# 06_-_SATA_CFAST.net
KiCad netlist of a schematic drawn in Altium Designer
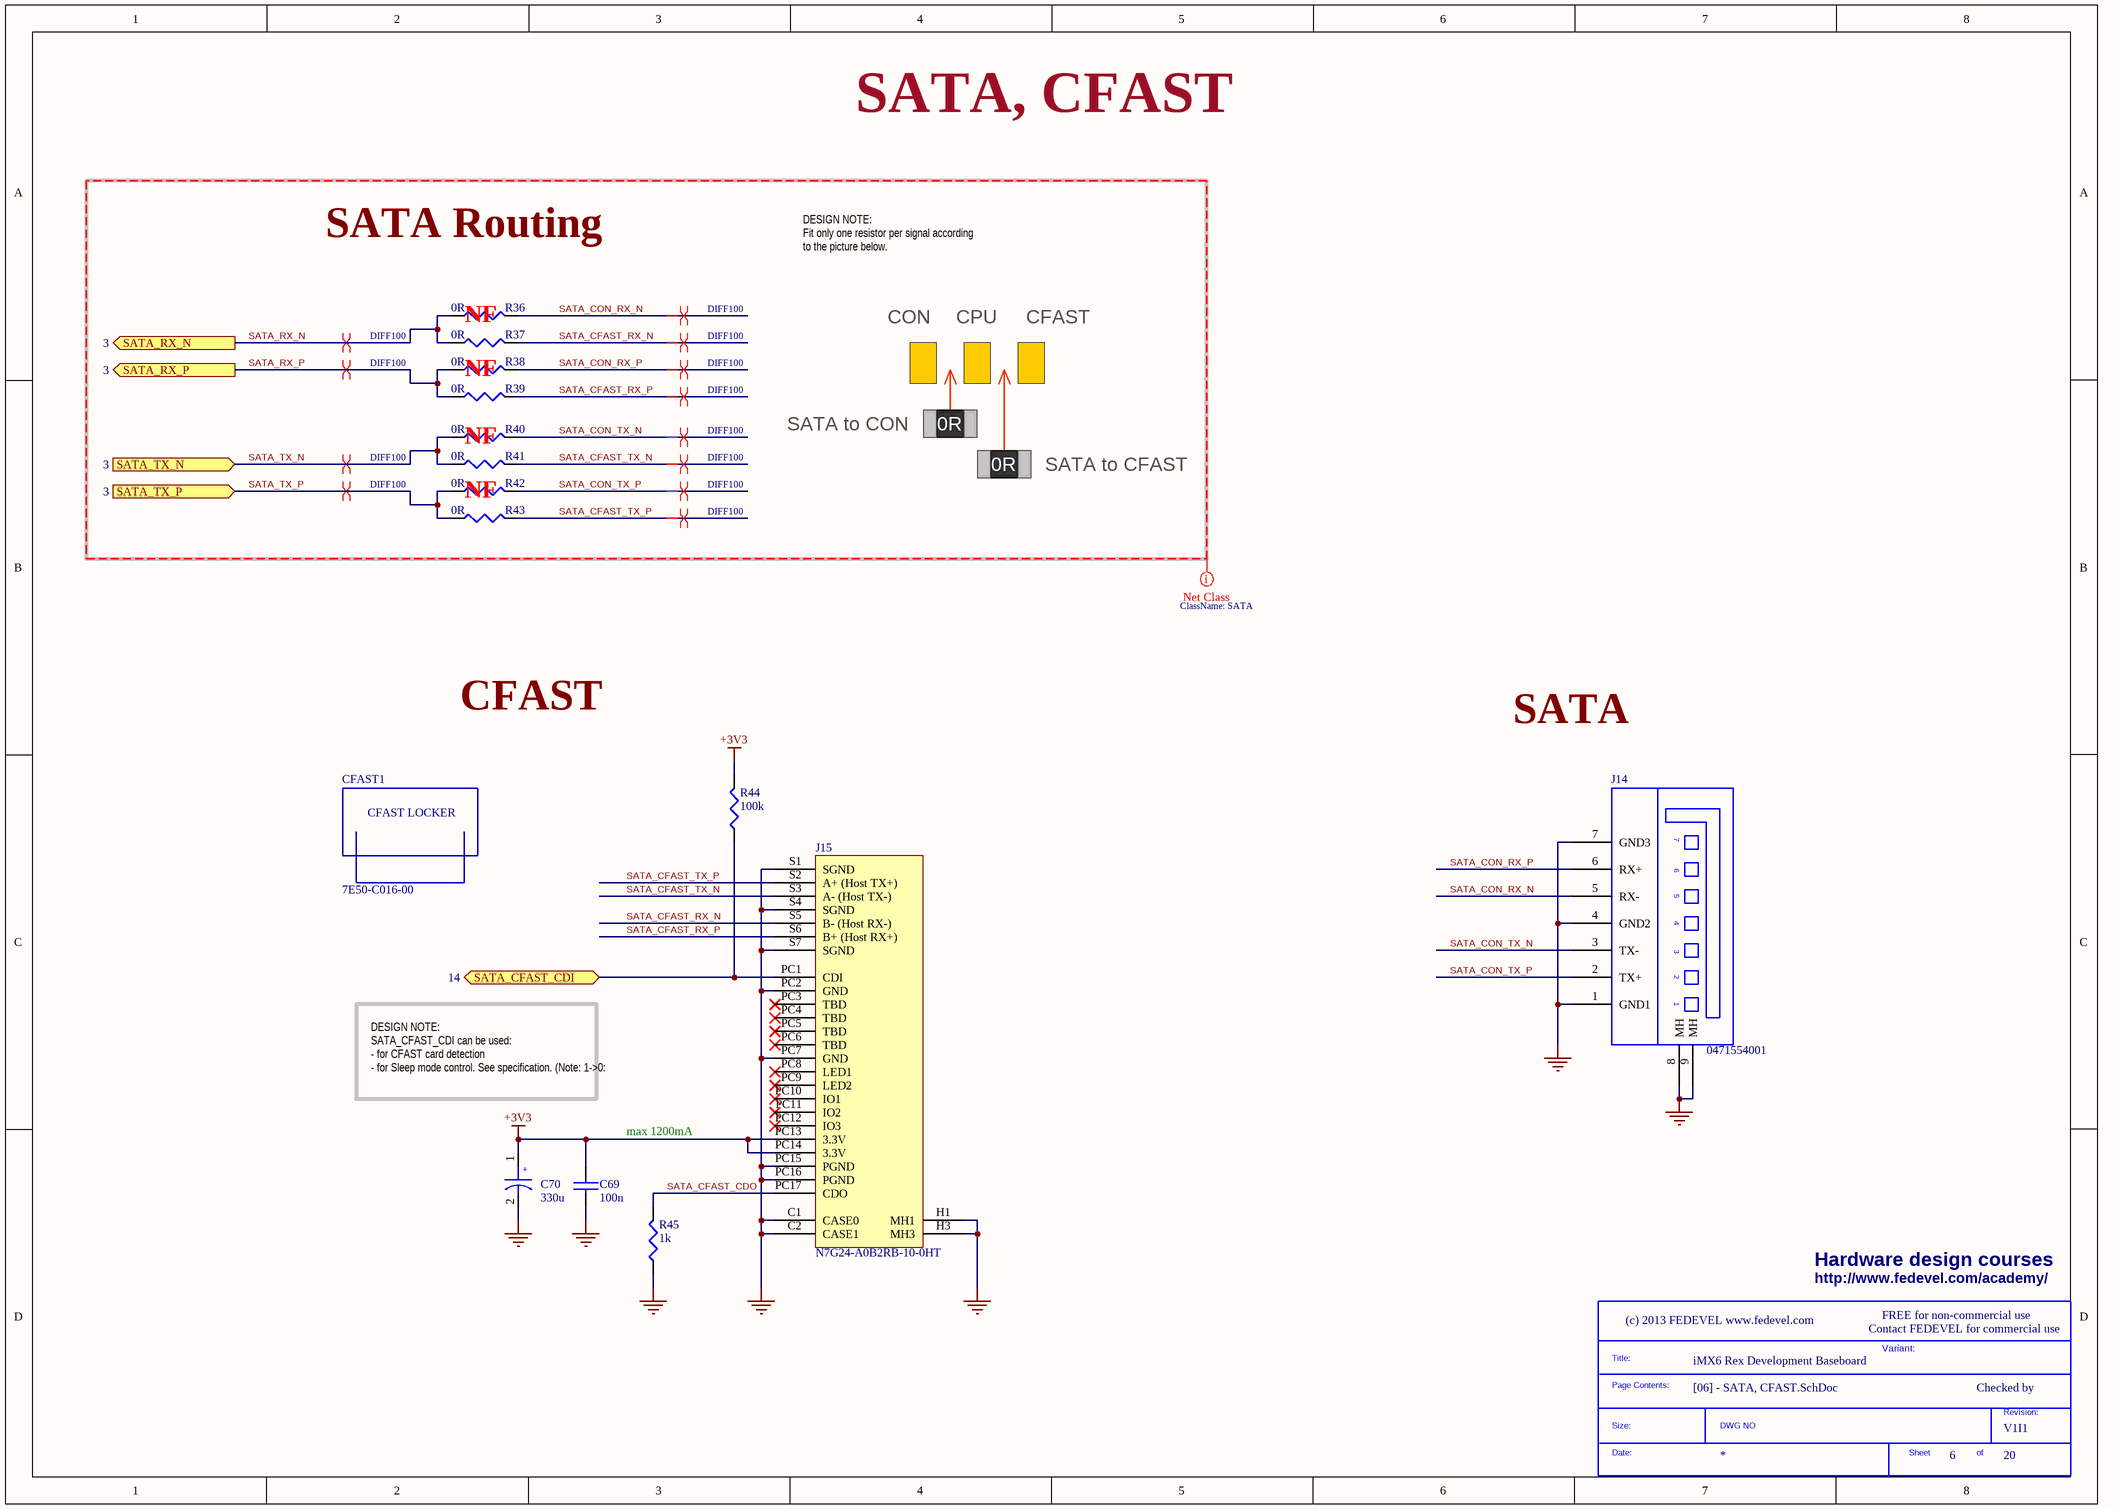
[diagram p0: [06] - SATA, CFAST.SchDoc]

(export (version "E")
  (design (tool "Eeschema 10.0.6"))
  (components
    (comp (ref "C69")
      (value "100n")
      (footprint "C0402")
      (description "CAP CER .10UF 50V X5R 10% 0402")
      (fields
        (field (name "MANUFACTURER") "TDK Corporation")
        (field (name "MANUFACTURER PART NUMBER") "C1005X5R1H104K")
      )
      (libsource (lib "Integrated_Library_RF_FEB_2012") (part "C1005X5R1H104K"))
    )
    (comp (ref "C70")
      (value "330u")
      (footprint "C2917")
      (description "CAP TANT 330UF 6.3V 20% 2917")
      (fields
        (field (name "MANUFACTURER") "Kemet")
        (field (name "MANUFACTURER PART NUMBER") "T520D337M006ATE045")
        (field (name ".CREATOR") "MM")
        (field (name ".CHECKED PCB") "MM")
        (field (name ".CHECKED SCH") "RF, used by MM")
      )
      (libsource (lib "Integrated_Library_RF_FEB_2012") (part "T520D337M006ATE045"))
    )
    (comp (ref "CFAST1")
      (value "7E50-C016-00")
      (footprint "CFAST_LOCKER")
      (description "CF CARD EJECT/LATCHING RETAINER")
      (fields
        (field (name "MANUFACTURER") "3M")
        (field (name ".CHECKED PCB") "RF")
        (field (name ".CHECKED SCH") "RF")
      )
      (libsource (lib "Integrated_Library_RF_FEB_2012") (part "7E50-C016-00"))
    )
    (comp (ref "J14")
      (value "0471554001")
      (footprint "SATA_VERTICAL")
      (description "CONN SATA HDR 7POS PCB VERT")
      (fields
        (field (name "MANUFACTURER") "Molex Inc")
        (field (name ".CHECKED PCB") "RF")
        (field (name ".CHECKED SCH") "RF")
      )
      (libsource (lib "Integrated_Library_RF_FEB_2012") (part "0471554001"))
    )
    (comp (ref "J15")
      (value "N7G24-A0B2RB-10-0HT")
      (footprint "CFAST10")
      (description "CFAST HEADER STANDOFF SMD R/A")
      (fields
        (field (name "MANUFACTURER") "3M")
        (field (name ".CHECKED PCB") "RF")
        (field (name ".CHECKED SCH") "RF")
      )
      (libsource (lib "Integrated_Library_RF_FEB_2012") (part "N7G24-A0B2RB-10-0HT"))
    )
    (comp (ref "R36")
      (value "0R")
      (footprint "R0402")
      (description "RES 0.0 OHM 1/16W 0402 SMD")
      (fields
        (field (name "MANUFACTURER") "Yageo")
        (field (name "MANUFACTURER PART NUMBER") "RC0402JR-070RL")
      )
      (libsource (lib "Integrated_Library_RF_FEB_2012") (part "RC0402JR-070RL"))
    )
    (comp (ref "R37")
      (value "0R")
      (footprint "R0402")
      (description "RES 0.0 OHM 1/16W 0402 SMD")
      (fields
        (field (name "MANUFACTURER") "Yageo")
        (field (name "MANUFACTURER PART NUMBER") "RC0402JR-070RL")
      )
      (libsource (lib "Integrated_Library_RF_FEB_2012") (part "RC0402JR-070RL"))
    )
    (comp (ref "R38")
      (value "0R")
      (footprint "R0402")
      (description "RES 0.0 OHM 1/16W 0402 SMD")
      (fields
        (field (name "MANUFACTURER") "Yageo")
        (field (name "MANUFACTURER PART NUMBER") "RC0402JR-070RL")
      )
      (libsource (lib "Integrated_Library_RF_FEB_2012") (part "RC0402JR-070RL"))
    )
    (comp (ref "R39")
      (value "0R")
      (footprint "R0402")
      (description "RES 0.0 OHM 1/16W 0402 SMD")
      (fields
        (field (name "MANUFACTURER") "Yageo")
        (field (name "MANUFACTURER PART NUMBER") "RC0402JR-070RL")
      )
      (libsource (lib "Integrated_Library_RF_FEB_2012") (part "RC0402JR-070RL"))
    )
    (comp (ref "R40")
      (value "0R")
      (footprint "R0402")
      (description "RES 0.0 OHM 1/16W 0402 SMD")
      (fields
        (field (name "MANUFACTURER") "Yageo")
        (field (name "MANUFACTURER PART NUMBER") "RC0402JR-070RL")
      )
      (libsource (lib "Integrated_Library_RF_FEB_2012") (part "RC0402JR-070RL"))
    )
    (comp (ref "R41")
      (value "0R")
      (footprint "R0402")
      (description "RES 0.0 OHM 1/16W 0402 SMD")
      (fields
        (field (name "MANUFACTURER") "Yageo")
        (field (name "MANUFACTURER PART NUMBER") "RC0402JR-070RL")
      )
      (libsource (lib "Integrated_Library_RF_FEB_2012") (part "RC0402JR-070RL"))
    )
    (comp (ref "R42")
      (value "0R")
      (footprint "R0402")
      (description "RES 0.0 OHM 1/16W 0402 SMD")
      (fields
        (field (name "MANUFACTURER") "Yageo")
        (field (name "MANUFACTURER PART NUMBER") "RC0402JR-070RL")
      )
      (libsource (lib "Integrated_Library_RF_FEB_2012") (part "RC0402JR-070RL"))
    )
    (comp (ref "R43")
      (value "0R")
      (footprint "R0402")
      (description "RES 0.0 OHM 1/16W 0402 SMD")
      (fields
        (field (name "MANUFACTURER") "Yageo")
        (field (name "MANUFACTURER PART NUMBER") "RC0402JR-070RL")
      )
      (libsource (lib "Integrated_Library_RF_FEB_2012") (part "RC0402JR-070RL"))
    )
    (comp (ref "R44")
      (value "100k")
      (footprint "R0402")
      (description "RES 100K OHM 1/16W 1% 0402 SMD")
      (fields
        (field (name "MANUFACTURER") "Stackpole Electronics Inc")
        (field (name "MANUFACTURER PART NUMBER") "RMCF0402FT100K")
      )
      (libsource (lib "Integrated_Library_RF_FEB_2012") (part "RMCF0402FT100K"))
    )
    (comp (ref "R45")
      (value "1k")
      (footprint "R0402")
      (description "RES 1.00K OHM 1/16W 1% 0402 SMD")
      (fields
        (field (name "MANUFACTURER") "Yageo")
        (field (name "MANUFACTURER PART NUMBER") "RC0402FR-071KL")
      )
      (libsource (lib "Integrated_Library_RF_FEB_2012") (part "RC0402FR-071KL"))
    )
  )
  (nets
    (net (code "1") (name "+3V3") (class "Default")
      (node (ref "C69") (pin "1") (pinfunction "1_1") (pintype "passive"))
      (node (ref "C70") (pin "1") (pinfunction "1_1") (pintype "passive"))
      (node (ref "J15") (pin "PC13") (pinfunction "3.3V_PC13") (pintype "passive"))
      (node (ref "J15") (pin "PC14") (pinfunction "3.3V_PC14") (pintype "passive"))
      (node (ref "R44") (pin "2") (pinfunction "2_2") (pintype "passive"))
    )
    (net (code "2") (name "/SATA_CFAST_CDI") (class "Default")
      (node (ref "J15") (pin "PC1") (pinfunction "CDI_PC1") (pintype "passive"))
      (node (ref "R44") (pin "1") (pinfunction "1_1") (pintype "passive"))
    )
    (net (code "3") (name "/SATA_CFAST_CDO") (class "Default")
      (node (ref "J15") (pin "PC17") (pinfunction "CDO_PC17") (pintype "passive"))
      (node (ref "R45") (pin "2") (pinfunction "2_2") (pintype "passive"))
    )
    (net (code "4") (name "/SATA_CFAST_RX_N") (class "Default")
      (node (ref "J15") (pin "S5") (pinfunction "B-_(Host_RX-)_S5") (pintype "passive"))
      (node (ref "R37") (pin "2") (pinfunction "2_2") (pintype "passive"))
    )
    (net (code "5") (name "/SATA_CFAST_RX_P") (class "Default")
      (node (ref "J15") (pin "S6") (pinfunction "B+_(Host_RX+)_S6") (pintype "passive"))
      (node (ref "R39") (pin "2") (pinfunction "2_2") (pintype "passive"))
    )
    (net (code "6") (name "/SATA_CFAST_TX_N") (class "Default")
      (node (ref "J15") (pin "S3") (pinfunction "A-_(Host_TX-)_S3") (pintype "passive"))
      (node (ref "R41") (pin "2") (pinfunction "2_2") (pintype "passive"))
    )
    (net (code "7") (name "/SATA_CFAST_TX_P") (class "Default")
      (node (ref "J15") (pin "S2") (pinfunction "A+_(Host_TX+)_S2") (pintype "passive"))
      (node (ref "R43") (pin "2") (pinfunction "2_2") (pintype "passive"))
    )
    (net (code "8") (name "/SATA_CON_RX_N") (class "Default")
      (node (ref "J14") (pin "5") (pinfunction "RX-_5") (pintype "passive"))
      (node (ref "R36") (pin "2") (pinfunction "2_2") (pintype "passive"))
    )
    (net (code "9") (name "/SATA_CON_RX_P") (class "Default")
      (node (ref "J14") (pin "6") (pinfunction "RX+_6") (pintype "passive"))
      (node (ref "R38") (pin "2") (pinfunction "2_2") (pintype "passive"))
    )
    (net (code "10") (name "/SATA_CON_TX_N") (class "Default")
      (node (ref "J14") (pin "3") (pinfunction "TX-_3") (pintype "passive"))
      (node (ref "R40") (pin "2") (pinfunction "2_2") (pintype "passive"))
    )
    (net (code "11") (name "/SATA_CON_TX_P") (class "Default")
      (node (ref "J14") (pin "2") (pinfunction "TX+_2") (pintype "passive"))
      (node (ref "R42") (pin "2") (pinfunction "2_2") (pintype "passive"))
    )
    (net (code "12") (name "/SATA_RX_N") (class "Default")
      (node (ref "R36") (pin "1") (pinfunction "1_1") (pintype "passive"))
      (node (ref "R37") (pin "1") (pinfunction "1_1") (pintype "passive"))
    )
    (net (code "13") (name "/SATA_RX_P") (class "Default")
      (node (ref "R38") (pin "1") (pinfunction "1_1") (pintype "passive"))
      (node (ref "R39") (pin "1") (pinfunction "1_1") (pintype "passive"))
    )
    (net (code "14") (name "/SATA_TX_N") (class "Default")
      (node (ref "R40") (pin "1") (pinfunction "1_1") (pintype "passive"))
      (node (ref "R41") (pin "1") (pinfunction "1_1") (pintype "passive"))
    )
    (net (code "15") (name "/SATA_TX_P") (class "Default")
      (node (ref "R42") (pin "1") (pinfunction "1_1") (pintype "passive"))
      (node (ref "R43") (pin "1") (pinfunction "1_1") (pintype "passive"))
    )
    (net (code "16") (name "GND") (class "Default")
      (node (ref "C69") (pin "2") (pinfunction "2_2") (pintype "passive"))
      (node (ref "C70") (pin "2") (pinfunction "2_2") (pintype "passive"))
      (node (ref "J14") (pin "1") (pinfunction "GND1_1") (pintype "passive"))
      (node (ref "J14") (pin "4") (pinfunction "GND2_4") (pintype "passive"))
      (node (ref "J14") (pin "7") (pinfunction "GND3_7") (pintype "passive"))
      (node (ref "J14") (pin "8") (pinfunction "MH_8") (pintype "passive"))
      (node (ref "J14") (pin "9") (pinfunction "MH_9") (pintype "passive"))
      (node (ref "J15") (pin "C1") (pinfunction "CASE0_C1") (pintype "passive"))
      (node (ref "J15") (pin "C2") (pinfunction "CASE1_C2") (pintype "passive"))
      (node (ref "J15") (pin "H1") (pinfunction "MH1_H1") (pintype "passive"))
      (node (ref "J15") (pin "H3") (pinfunction "MH3_H3") (pintype "passive"))
      (node (ref "J15") (pin "PC15") (pinfunction "PGND_PC15") (pintype "passive"))
      (node (ref "J15") (pin "PC16") (pinfunction "PGND_PC16") (pintype "passive"))
      (node (ref "J15") (pin "PC2") (pinfunction "GND_PC2") (pintype "passive"))
      (node (ref "J15") (pin "PC7") (pinfunction "GND_PC7") (pintype "passive"))
      (node (ref "J15") (pin "S1") (pinfunction "SGND_S1") (pintype "passive"))
      (node (ref "J15") (pin "S4") (pinfunction "SGND_S4") (pintype "passive"))
      (node (ref "J15") (pin "S7") (pinfunction "SGND_S7") (pintype "passive"))
      (node (ref "R45") (pin "1") (pinfunction "1_1") (pintype "passive"))
    )
    (net (code "17") (name "unconnected-(J15-IO1-PadPC10)") (class "Default")
      (node (ref "J15") (pin "PC10") (pinfunction "IO1_PC10") (pintype "passive+no_connect"))
    )
    (net (code "18") (name "unconnected-(J15-IO2-PadPC11)") (class "Default")
      (node (ref "J15") (pin "PC11") (pinfunction "IO2_PC11") (pintype "passive+no_connect"))
    )
    (net (code "19") (name "unconnected-(J15-IO3-PadPC12)") (class "Default")
      (node (ref "J15") (pin "PC12") (pinfunction "IO3_PC12") (pintype "passive+no_connect"))
    )
    (net (code "20") (name "unconnected-(J15-LED1-PadPC8)") (class "Default")
      (node (ref "J15") (pin "PC8") (pinfunction "LED1_PC8") (pintype "passive+no_connect"))
    )
    (net (code "21") (name "unconnected-(J15-LED2-PadPC9)") (class "Default")
      (node (ref "J15") (pin "PC9") (pinfunction "LED2_PC9") (pintype "passive+no_connect"))
    )
    (net (code "22") (name "unconnected-(J15-PadH2)") (class "Default")
      (node (ref "J15") (pin "H2") (pinfunction "H2_H2") (pintype "passive"))
    )
    (net (code "23") (name "unconnected-(J15-PadH4)") (class "Default")
      (node (ref "J15") (pin "H4") (pinfunction "H4_H4") (pintype "passive"))
    )
    (net (code "24") (name "unconnected-(J15-PadH5)") (class "Default")
      (node (ref "J15") (pin "H5") (pinfunction "H5_H5") (pintype "passive"))
    )
    (net (code "25") (name "unconnected-(J15-PadH6)") (class "Default")
      (node (ref "J15") (pin "H6") (pinfunction "H6_H6") (pintype "passive"))
    )
    (net (code "26") (name "unconnected-(J15-TBD-PadPC3)") (class "Default")
      (node (ref "J15") (pin "PC3") (pinfunction "TBD_PC3") (pintype "passive+no_connect"))
    )
    (net (code "27") (name "unconnected-(J15-TBD-PadPC4)") (class "Default")
      (node (ref "J15") (pin "PC4") (pinfunction "TBD_PC4") (pintype "passive+no_connect"))
    )
    (net (code "28") (name "unconnected-(J15-TBD-PadPC5)") (class "Default")
      (node (ref "J15") (pin "PC5") (pinfunction "TBD_PC5") (pintype "passive+no_connect"))
    )
    (net (code "29") (name "unconnected-(J15-TBD-PadPC6)") (class "Default")
      (node (ref "J15") (pin "PC6") (pinfunction "TBD_PC6") (pintype "passive+no_connect"))
    )
  )
)
